# Onion_O2S_mPCIe.net
KiCad netlist of a schematic drawn in EAGLE
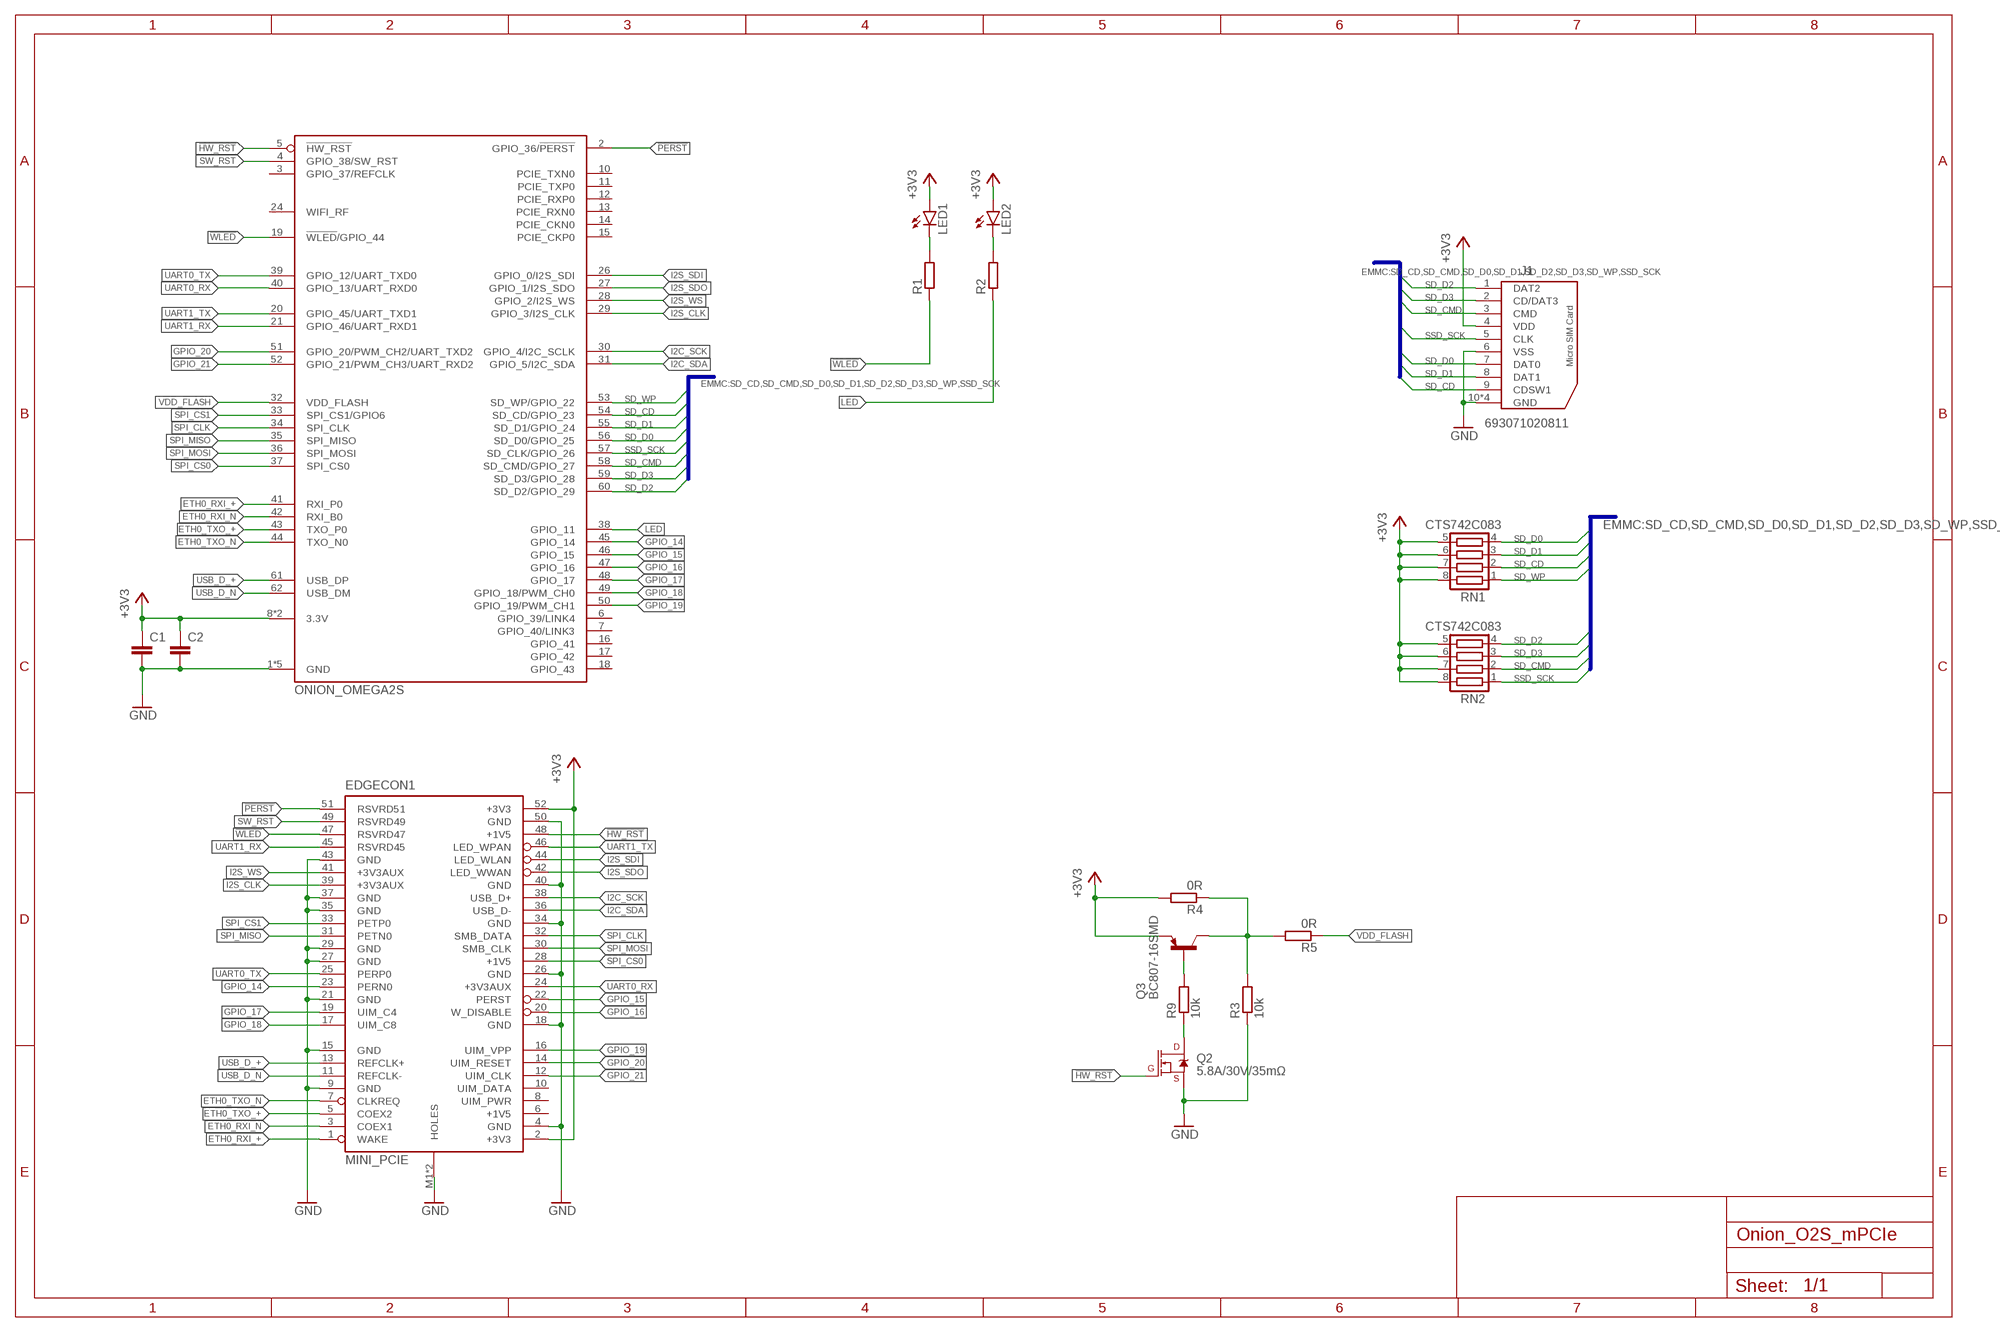
[diagram p0: schematic, sheet 1]

(export (version "E")
  (design (tool "Eeschema 10.0.6"))
  (components
    (comp (ref "C1")
      (value "C-EUC0603")
      (footprint "eagle-import:C0603")
      (libsource (lib "eagle-import") (part "C-EUC0603"))
    )
    (comp (ref "C2")
      (value "C-EUC0603")
      (footprint "eagle-import:C0603")
      (libsource (lib "eagle-import") (part "C-EUC0603"))
    )
    (comp (ref "EDGECON1")
      (value "MINI_PCIE")
      (footprint "eagle-import:MINI_PCIE")
      (libsource (lib "eagle-import") (part "MINI_PCIE"))
    )
    (comp (ref "J1")
      (value "693071020811")
      (footprint "eagle-import:693071020811")
      (libsource (lib "eagle-import") (part "693071020811"))
    )
    (comp (ref "LED1")
      (value "LEDCHIPLED_0603")
      (footprint "eagle-import:CHIPLED_0603")
      (libsource (lib "eagle-import") (part "LEDCHIPLED_0603"))
    )
    (comp (ref "LED2")
      (value "LEDCHIPLED_0603")
      (footprint "eagle-import:CHIPLED_0603")
      (libsource (lib "eagle-import") (part "LEDCHIPLED_0603"))
    )
    (comp (ref "Q2")
      (value "5.8A/30V/35mΩ")
      (footprint "eagle-import:SOT23-3")
      (libsource (lib "eagle-import") (part "MOSFET-NCH-AO3404A"))
    )
    (comp (ref "Q3")
      (value "BC807-16SMD")
      (footprint "eagle-import:SOT23-BEC")
      (libsource (lib "eagle-import") (part "BC807SMD-16"))
    )
    (comp (ref "R1")
      (value "R-EU_R0603")
      (footprint "eagle-import:R0603")
      (libsource (lib "eagle-import") (part "rcl_44894963_R-EU_R0603"))
    )
    (comp (ref "R2")
      (value "R-EU_R0603")
      (footprint "eagle-import:R0603")
      (libsource (lib "eagle-import") (part "rcl_44894963_R-EU_R0603"))
    )
    (comp (ref "R3")
      (value "10k")
      (footprint "eagle-import:R0603")
      (libsource (lib "eagle-import") (part "R-EU_R0603"))
    )
    (comp (ref "R4")
      (value "0R")
      (footprint "eagle-import:R0603")
      (libsource (lib "eagle-import") (part "R-EU_R0603"))
    )
    (comp (ref "R5")
      (value "0R")
      (footprint "eagle-import:R0603")
      (libsource (lib "eagle-import") (part "R-EU_R0603"))
    )
    (comp (ref "R9")
      (value "10k")
      (footprint "eagle-import:R0603")
      (libsource (lib "eagle-import") (part "R-EU_R0603"))
    )
    (comp (ref "RN1")
      (value "CTS742C083")
      (footprint "eagle-import:CTS742C083")
      (libsource (lib "eagle-import") (part "CTS742C083"))
    )
    (comp (ref "RN2")
      (value "CTS742C083")
      (footprint "eagle-import:CTS742C083")
      (libsource (lib "eagle-import") (part "CTS742C083"))
    )
    (comp (ref "U1")
      (value "ONION_OMEGA2S")
      (footprint "eagle-import:ONION_OMEGA2S")
      (libsource (lib "eagle-import") (part "ONION_OMEGA2S"))
    )
  )
  (nets
    (net (code "2") (name "+3V3") (class "Default")
      (node (ref "C1") (pin "1") (pinfunction "1_1") (pintype "passive"))
      (node (ref "C2") (pin "1") (pinfunction "1_1") (pintype "passive"))
      (node (ref "EDGECON1") (pin "2") (pinfunction "+3V3_2") (pintype "power_in"))
      (node (ref "EDGECON1") (pin "52") (pinfunction "+3V3_52") (pintype "power_in"))
      (node (ref "J1") (pin "4") (pinfunction "VDD_4") (pintype "bidirectional"))
      (node (ref "LED1") (pin "A") (pinfunction "A_A") (pintype "passive"))
      (node (ref "LED2") (pin "A") (pinfunction "A_A") (pintype "passive"))
      (node (ref "Q3") (pin "E") (pinfunction "E_E") (pintype "passive"))
      (node (ref "R4") (pin "2") (pinfunction "2_2") (pintype "passive"))
      (node (ref "RN1") (pin "5") (pinfunction "5_5") (pintype "passive"))
      (node (ref "RN1") (pin "6") (pinfunction "6_6") (pintype "passive"))
      (node (ref "RN1") (pin "7") (pinfunction "7_7") (pintype "passive"))
      (node (ref "RN1") (pin "8") (pinfunction "8_8") (pintype "passive"))
      (node (ref "RN2") (pin "5") (pinfunction "5_5") (pintype "passive"))
      (node (ref "RN2") (pin "6") (pinfunction "6_6") (pintype "passive"))
      (node (ref "RN2") (pin "7") (pinfunction "7_7") (pintype "passive"))
      (node (ref "RN2") (pin "8") (pinfunction "8_8") (pintype "passive"))
      (node (ref "U1") (pin "8") (pinfunction "3.3V_8") (pintype "bidirectional"))
      (node (ref "U1") (pin "9") (pinfunction "3.3V_9") (pintype "bidirectional"))
    )
    (net (code "3") (name "/+1V5") (class "Default")
      (node (ref "EDGECON1") (pin "6") (pinfunction "+1V5_6") (pintype "power_in"))
    )
    (net (code "4") (name "/SD_CD") (class "Default")
      (node (ref "J1") (pin "9") (pinfunction "CDSW1_9") (pintype "bidirectional"))
      (node (ref "RN1") (pin "2") (pinfunction "2_2") (pintype "passive"))
      (node (ref "U1") (pin "54") (pinfunction "SD_CD/GPIO_23_54") (pintype "bidirectional"))
    )
    (net (code "5") (name "/SD_CMD") (class "Default")
      (node (ref "J1") (pin "3") (pinfunction "CMD_3") (pintype "bidirectional"))
      (node (ref "RN2") (pin "2") (pinfunction "2_2") (pintype "passive"))
      (node (ref "U1") (pin "58") (pinfunction "SD_CMD/GPIO_27_58") (pintype "bidirectional"))
    )
    (net (code "6") (name "/SD_D0") (class "Default")
      (node (ref "J1") (pin "7") (pinfunction "DAT0_7") (pintype "bidirectional"))
      (node (ref "RN1") (pin "4") (pinfunction "4_4") (pintype "passive"))
      (node (ref "U1") (pin "56") (pinfunction "SD_D0/GPIO_25_56") (pintype "bidirectional"))
    )
    (net (code "7") (name "/SD_D1") (class "Default")
      (node (ref "J1") (pin "8") (pinfunction "DAT1_8") (pintype "bidirectional"))
      (node (ref "RN1") (pin "3") (pinfunction "3_3") (pintype "passive"))
      (node (ref "U1") (pin "55") (pinfunction "SD_D1/GPIO_24_55") (pintype "bidirectional"))
    )
    (net (code "8") (name "/SD_D2") (class "Default")
      (node (ref "J1") (pin "1") (pinfunction "DAT2_1") (pintype "bidirectional"))
      (node (ref "RN2") (pin "4") (pinfunction "4_4") (pintype "passive"))
      (node (ref "U1") (pin "60") (pinfunction "SD_D2/GPIO_29_60") (pintype "bidirectional"))
    )
    (net (code "9") (name "/SD_D3") (class "Default")
      (node (ref "J1") (pin "2") (pinfunction "CD/DAT3_2") (pintype "bidirectional"))
      (node (ref "RN2") (pin "3") (pinfunction "3_3") (pintype "passive"))
      (node (ref "U1") (pin "59") (pinfunction "SD_D3/GPIO_28_59") (pintype "bidirectional"))
    )
    (net (code "10") (name "/SD_WP") (class "Default")
      (node (ref "RN1") (pin "1") (pinfunction "1_1") (pintype "passive"))
      (node (ref "U1") (pin "53") (pinfunction "SD_WP/GPIO_22_53") (pintype "bidirectional"))
    )
    (net (code "11") (name "/SSD_SCK") (class "Default")
      (node (ref "J1") (pin "5") (pinfunction "CLK_5") (pintype "bidirectional"))
      (node (ref "RN2") (pin "1") (pinfunction "1_1") (pintype "passive"))
      (node (ref "U1") (pin "57") (pinfunction "SD_CLK/GPIO_26_57") (pintype "bidirectional"))
    )
    (net (code "13") (name "/~{HW_RST}") (class "Default")
      (node (ref "EDGECON1") (pin "48") (pinfunction "+1V5_48") (pintype "output"))
      (node (ref "Q2") (pin "1") (pinfunction "G_1") (pintype "bidirectional"))
      (node (ref "U1") (pin "5") (pinfunction "~{HW_RST}_5") (pintype "bidirectional"))
    )
    (net (code "14") (name "/~{PERST}") (class "Default")
      (node (ref "EDGECON1") (pin "51") (pinfunction "RSVRD51_51") (pintype "bidirectional"))
      (node (ref "U1") (pin "2") (pinfunction "GPIO_36/~{PERST}_2") (pintype "bidirectional"))
    )
    (net (code "15") (name "/~{WLED}") (class "Default")
      (node (ref "EDGECON1") (pin "47") (pinfunction "RSVRD47_47") (pintype "bidirectional"))
      (node (ref "R1") (pin "1") (pinfunction "1_1") (pintype "passive"))
      (node (ref "U1") (pin "19") (pinfunction "~{WLED}/GPIO_44_19") (pintype "bidirectional"))
    )
    (net (code "16") (name "ETH0_RXI_+") (class "Default")
      (node (ref "EDGECON1") (pin "1") (pinfunction "WAKE_1") (pintype "output"))
      (node (ref "U1") (pin "41") (pinfunction "RXI_P0_41") (pintype "bidirectional"))
    )
    (net (code "17") (name "ETH0_RXI_N") (class "Default")
      (node (ref "EDGECON1") (pin "3") (pinfunction "COEX1_3") (pintype "bidirectional"))
      (node (ref "U1") (pin "42") (pinfunction "RXI_B0_42") (pintype "bidirectional"))
    )
    (net (code "18") (name "ETH0_TXO_+") (class "Default")
      (node (ref "EDGECON1") (pin "5") (pinfunction "COEX2_5") (pintype "bidirectional"))
      (node (ref "U1") (pin "43") (pinfunction "TXO_P0_43") (pintype "bidirectional"))
    )
    (net (code "19") (name "ETH0_TXO_N") (class "Default")
      (node (ref "EDGECON1") (pin "7") (pinfunction "CLKREQ_7") (pintype "output"))
      (node (ref "U1") (pin "44") (pinfunction "TXO_N0_44") (pintype "bidirectional"))
    )
    (net (code "20") (name "GND") (class "Default")
      (node (ref "C1") (pin "2") (pinfunction "2_2") (pintype "passive"))
      (node (ref "C2") (pin "2") (pinfunction "2_2") (pintype "passive"))
      (node (ref "EDGECON1") (pin "15") (pinfunction "GND_15") (pintype "power_in"))
      (node (ref "EDGECON1") (pin "18") (pinfunction "GND_18") (pintype "power_in"))
      (node (ref "EDGECON1") (pin "21") (pinfunction "GND_21") (pintype "power_in"))
      (node (ref "EDGECON1") (pin "26") (pinfunction "GND_26") (pintype "power_in"))
      (node (ref "EDGECON1") (pin "27") (pinfunction "GND_27") (pintype "power_in"))
      (node (ref "EDGECON1") (pin "29") (pinfunction "GND_29") (pintype "power_in"))
      (node (ref "EDGECON1") (pin "34") (pinfunction "GND_34") (pintype "bidirectional"))
      (node (ref "EDGECON1") (pin "35") (pinfunction "GND_35") (pintype "power_in"))
      (node (ref "EDGECON1") (pin "37") (pinfunction "GND_37") (pintype "bidirectional"))
      (node (ref "EDGECON1") (pin "4") (pinfunction "GND_4") (pintype "power_in"))
      (node (ref "EDGECON1") (pin "40") (pinfunction "GND_40") (pintype "bidirectional"))
      (node (ref "EDGECON1") (pin "43") (pinfunction "GND_43") (pintype "bidirectional"))
      (node (ref "EDGECON1") (pin "50") (pinfunction "GND_50") (pintype "output"))
      (node (ref "EDGECON1") (pin "9") (pinfunction "GND_9") (pintype "power_in"))
      (node (ref "EDGECON1") (pin "M1") (pinfunction "HOLES_M1") (pintype "bidirectional"))
      (node (ref "EDGECON1") (pin "M2") (pinfunction "HOLES_M2") (pintype "bidirectional"))
      (node (ref "J1") (pin "10") (pinfunction "GND_10") (pintype "bidirectional"))
      (node (ref "J1") (pin "11") (pinfunction "GND_11") (pintype "bidirectional"))
      (node (ref "J1") (pin "12") (pinfunction "GND_12") (pintype "bidirectional"))
      (node (ref "J1") (pin "13") (pinfunction "GND_13") (pintype "bidirectional"))
      (node (ref "J1") (pin "6") (pinfunction "VSS_6") (pintype "bidirectional"))
      (node (ref "Q2") (pin "2") (pinfunction "S_2") (pintype "bidirectional"))
      (node (ref "R3") (pin "1") (pinfunction "1_1") (pintype "passive"))
      (node (ref "U1") (pin "1") (pinfunction "GND_1") (pintype "bidirectional"))
      (node (ref "U1") (pin "22") (pinfunction "GND_22") (pintype "bidirectional"))
      (node (ref "U1") (pin "23") (pinfunction "GND_23") (pintype "bidirectional"))
      (node (ref "U1") (pin "25") (pinfunction "GND_25") (pintype "bidirectional"))
      (node (ref "U1") (pin "63") (pinfunction "GND_63") (pintype "bidirectional"))
    )
    (net (code "21") (name "GPIO_14") (class "Default")
      (node (ref "EDGECON1") (pin "23") (pinfunction "PERN0_23") (pintype "bidirectional"))
      (node (ref "U1") (pin "45") (pinfunction "GPIO_14_45") (pintype "bidirectional"))
    )
    (net (code "22") (name "GPIO_15") (class "Default")
      (node (ref "EDGECON1") (pin "22") (pinfunction "PERST_22") (pintype "input"))
      (node (ref "U1") (pin "46") (pinfunction "GPIO_15_46") (pintype "bidirectional"))
    )
    (net (code "23") (name "GPIO_16") (class "Default")
      (node (ref "EDGECON1") (pin "20") (pinfunction "W_DISABLE_20") (pintype "input"))
      (node (ref "U1") (pin "47") (pinfunction "GPIO_16_47") (pintype "bidirectional"))
    )
    (net (code "24") (name "GPIO_17") (class "Default")
      (node (ref "EDGECON1") (pin "19") (pinfunction "UIM_C4_19") (pintype "bidirectional"))
      (node (ref "U1") (pin "48") (pinfunction "GPIO_17_48") (pintype "bidirectional"))
    )
    (net (code "25") (name "GPIO_18") (class "Default")
      (node (ref "EDGECON1") (pin "17") (pinfunction "UIM_C8_17") (pintype "bidirectional"))
      (node (ref "U1") (pin "49") (pinfunction "GPIO_18/PWM_CH0_49") (pintype "bidirectional"))
    )
    (net (code "26") (name "GPIO_19") (class "Default")
      (node (ref "EDGECON1") (pin "16") (pinfunction "UIM_VPP_16") (pintype "bidirectional"))
      (node (ref "U1") (pin "50") (pinfunction "GPIO_19/PWM_CH1_50") (pintype "bidirectional"))
    )
    (net (code "27") (name "GPIO_20") (class "Default")
      (node (ref "EDGECON1") (pin "14") (pinfunction "UIM_RESET_14") (pintype "bidirectional"))
      (node (ref "U1") (pin "51") (pinfunction "GPIO_20/PWM_CH2/UART_TXD2_51") (pintype "bidirectional"))
    )
    (net (code "28") (name "GPIO_21") (class "Default")
      (node (ref "EDGECON1") (pin "12") (pinfunction "UIM_CLK_12") (pintype "bidirectional"))
      (node (ref "U1") (pin "52") (pinfunction "GPIO_21/PWM_CH3/UART_RXD2_52") (pintype "bidirectional"))
    )
    (net (code "29") (name "I2C_SCK") (class "Default")
      (node (ref "EDGECON1") (pin "38") (pinfunction "USB_D+_38") (pintype "power_in"))
      (node (ref "U1") (pin "30") (pinfunction "GPIO_4/I2C_SCLK_30") (pintype "bidirectional"))
    )
    (net (code "30") (name "I2C_SDA") (class "Default")
      (node (ref "EDGECON1") (pin "36") (pinfunction "USB_D-_36") (pintype "bidirectional"))
      (node (ref "U1") (pin "31") (pinfunction "GPIO_5/I2C_SDA_31") (pintype "bidirectional"))
    )
    (net (code "31") (name "I2S_CLK") (class "Default")
      (node (ref "EDGECON1") (pin "39") (pinfunction "+3V3AUX_39") (pintype "bidirectional"))
      (node (ref "U1") (pin "29") (pinfunction "GPIO_3/I2S_CLK_29") (pintype "bidirectional"))
    )
    (net (code "32") (name "I2S_SDI") (class "Default")
      (node (ref "EDGECON1") (pin "44") (pinfunction "LED_WLAN_44") (pintype "output"))
      (node (ref "U1") (pin "26") (pinfunction "GPIO_0/I2S_SDI_26") (pintype "bidirectional"))
    )
    (net (code "33") (name "I2S_SDO") (class "Default")
      (node (ref "EDGECON1") (pin "42") (pinfunction "LED_WWAN_42") (pintype "output"))
      (node (ref "U1") (pin "27") (pinfunction "GPIO_1/I2S_SDO_27") (pintype "bidirectional"))
    )
    (net (code "34") (name "I2S_WS") (class "Default")
      (node (ref "EDGECON1") (pin "41") (pinfunction "+3V3AUX_41") (pintype "bidirectional"))
      (node (ref "U1") (pin "28") (pinfunction "GPIO_2/I2S_WS_28") (pintype "bidirectional"))
    )
    (net (code "35") (name "LED") (class "Default")
      (node (ref "R2") (pin "1") (pinfunction "1_1") (pintype "passive"))
      (node (ref "U1") (pin "38") (pinfunction "GPIO_11_38") (pintype "bidirectional"))
    )
    (net (code "36") (name "Net-(LED1-PadC)") (class "Default")
      (node (ref "LED1") (pin "C") (pinfunction "C_C") (pintype "passive"))
      (node (ref "R1") (pin "2") (pinfunction "2_2") (pintype "passive"))
    )
    (net (code "37") (name "Net-(LED2-PadC)") (class "Default")
      (node (ref "LED2") (pin "C") (pinfunction "C_C") (pintype "passive"))
      (node (ref "R2") (pin "2") (pinfunction "2_2") (pintype "passive"))
    )
    (net (code "38") (name "Net-(Q2-D)") (class "Default")
      (node (ref "Q2") (pin "3") (pinfunction "D_3") (pintype "bidirectional"))
      (node (ref "R9") (pin "1") (pinfunction "1_1") (pintype "passive"))
    )
    (net (code "39") (name "Net-(Q3-PadB)") (class "Default")
      (node (ref "Q3") (pin "B") (pinfunction "B_B") (pintype "passive"))
      (node (ref "R9") (pin "2") (pinfunction "2_2") (pintype "passive"))
    )
    (net (code "40") (name "Net-(Q3-PadC)") (class "Default")
      (node (ref "Q3") (pin "C") (pinfunction "C_C") (pintype "passive"))
      (node (ref "R3") (pin "2") (pinfunction "2_2") (pintype "passive"))
      (node (ref "R4") (pin "1") (pinfunction "1_1") (pintype "passive"))
      (node (ref "R5") (pin "2") (pinfunction "2_2") (pintype "passive"))
    )
    (net (code "41") (name "SPI_CLK") (class "Default")
      (node (ref "EDGECON1") (pin "32") (pinfunction "SMB_DATA_32") (pintype "power_in"))
      (node (ref "U1") (pin "34") (pinfunction "SPI_CLK_34") (pintype "bidirectional"))
    )
    (net (code "42") (name "SPI_CS0") (class "Default")
      (node (ref "EDGECON1") (pin "28") (pinfunction "+1V5_28") (pintype "power_in"))
      (node (ref "U1") (pin "37") (pinfunction "SPI_CS0_37") (pintype "bidirectional"))
    )
    (net (code "43") (name "SPI_CS1") (class "Default")
      (node (ref "EDGECON1") (pin "33") (pinfunction "PETP0_33") (pintype "bidirectional"))
      (node (ref "U1") (pin "33") (pinfunction "SPI_CS1/GPIO6_33") (pintype "bidirectional"))
    )
    (net (code "44") (name "SPI_MISO") (class "Default")
      (node (ref "EDGECON1") (pin "31") (pinfunction "PETN0_31") (pintype "bidirectional"))
      (node (ref "U1") (pin "35") (pinfunction "SPI_MISO_35") (pintype "bidirectional"))
    )
    (net (code "45") (name "SPI_MOSI") (class "Default")
      (node (ref "EDGECON1") (pin "30") (pinfunction "SMB_CLK_30") (pintype "input"))
      (node (ref "U1") (pin "36") (pinfunction "SPI_MOSI_36") (pintype "bidirectional"))
    )
    (net (code "46") (name "SW_RST") (class "Default")
      (node (ref "EDGECON1") (pin "49") (pinfunction "RSVRD49_49") (pintype "bidirectional"))
      (node (ref "U1") (pin "4") (pinfunction "GPIO_38/SW_RST_4") (pintype "bidirectional"))
    )
    (net (code "47") (name "UART0_RX") (class "Default")
      (node (ref "EDGECON1") (pin "24") (pinfunction "+3V3AUX_24") (pintype "power_in"))
      (node (ref "U1") (pin "40") (pinfunction "GPIO_13/UART_RXD0_40") (pintype "bidirectional"))
    )
    (net (code "48") (name "UART0_TX") (class "Default")
      (node (ref "EDGECON1") (pin "25") (pinfunction "PERP0_25") (pintype "bidirectional"))
      (node (ref "U1") (pin "39") (pinfunction "GPIO_12/UART_TXD0_39") (pintype "bidirectional"))
    )
    (net (code "49") (name "UART1_RX") (class "Default")
      (node (ref "EDGECON1") (pin "45") (pinfunction "RSVRD45_45") (pintype "bidirectional"))
      (node (ref "U1") (pin "21") (pinfunction "GPIO_46/UART_RXD1_21") (pintype "bidirectional"))
    )
    (net (code "50") (name "UART1_TX") (class "Default")
      (node (ref "EDGECON1") (pin "46") (pinfunction "LED_WPAN_46") (pintype "output"))
      (node (ref "U1") (pin "20") (pinfunction "GPIO_45/UART_TXD1_20") (pintype "bidirectional"))
    )
    (net (code "51") (name "USB_D_+") (class "Default")
      (node (ref "EDGECON1") (pin "13") (pinfunction "REFCLK+_13") (pintype "input"))
      (node (ref "U1") (pin "61") (pinfunction "USB_DP_61") (pintype "bidirectional"))
    )
    (net (code "52") (name "USB_D_N") (class "Default")
      (node (ref "EDGECON1") (pin "11") (pinfunction "REFCLK-_11") (pintype "input"))
      (node (ref "U1") (pin "62") (pinfunction "USB_DM_62") (pintype "bidirectional"))
    )
    (net (code "53") (name "VDD_FLASH") (class "Default")
      (node (ref "R5") (pin "1") (pinfunction "1_1") (pintype "passive"))
      (node (ref "U1") (pin "32") (pinfunction "VDD_FLASH_32") (pintype "bidirectional"))
    )
    (net (code "54") (name "unconnected-(EDGECON1-UIM_DATA-Pad10)") (class "Default")
      (node (ref "EDGECON1") (pin "10") (pinfunction "UIM_DATA_10") (pintype "bidirectional"))
    )
    (net (code "55") (name "unconnected-(EDGECON1-UIM_PWR-Pad8)") (class "Default")
      (node (ref "EDGECON1") (pin "8") (pinfunction "UIM_PWR_8") (pintype "bidirectional"))
    )
    (net (code "56") (name "unconnected-(U1-GPIO_37{slash}REFCLK-Pad3)") (class "Default")
      (node (ref "U1") (pin "3") (pinfunction "GPIO_37/REFCLK_3") (pintype "bidirectional"))
    )
    (net (code "57") (name "unconnected-(U1-GPIO_39{slash}LINK4-Pad6)") (class "Default")
      (node (ref "U1") (pin "6") (pinfunction "GPIO_39/LINK4_6") (pintype "bidirectional"))
    )
    (net (code "58") (name "unconnected-(U1-GPIO_40{slash}LINK3-Pad7)") (class "Default")
      (node (ref "U1") (pin "7") (pinfunction "GPIO_40/LINK3_7") (pintype "bidirectional"))
    )
    (net (code "59") (name "unconnected-(U1-GPIO_41-Pad16)") (class "Default")
      (node (ref "U1") (pin "16") (pinfunction "GPIO_41_16") (pintype "bidirectional"))
    )
    (net (code "60") (name "unconnected-(U1-GPIO_42-Pad17)") (class "Default")
      (node (ref "U1") (pin "17") (pinfunction "GPIO_42_17") (pintype "bidirectional"))
    )
    (net (code "61") (name "unconnected-(U1-GPIO_43-Pad18)") (class "Default")
      (node (ref "U1") (pin "18") (pinfunction "GPIO_43_18") (pintype "bidirectional"))
    )
    (net (code "62") (name "unconnected-(U1-PCIE_CKN0-Pad14)") (class "Default")
      (node (ref "U1") (pin "14") (pinfunction "PCIE_CKN0_14") (pintype "bidirectional"))
    )
    (net (code "63") (name "unconnected-(U1-PCIE_CKP0-Pad15)") (class "Default")
      (node (ref "U1") (pin "15") (pinfunction "PCIE_CKP0_15") (pintype "bidirectional"))
    )
    (net (code "64") (name "unconnected-(U1-PCIE_RXN0-Pad13)") (class "Default")
      (node (ref "U1") (pin "13") (pinfunction "PCIE_RXN0_13") (pintype "bidirectional"))
    )
    (net (code "65") (name "unconnected-(U1-PCIE_RXP0-Pad12)") (class "Default")
      (node (ref "U1") (pin "12") (pinfunction "PCIE_RXP0_12") (pintype "bidirectional"))
    )
    (net (code "66") (name "unconnected-(U1-PCIE_TXN0-Pad10)") (class "Default")
      (node (ref "U1") (pin "10") (pinfunction "PCIE_TXN0_10") (pintype "bidirectional"))
    )
    (net (code "67") (name "unconnected-(U1-PCIE_TXP0-Pad11)") (class "Default")
      (node (ref "U1") (pin "11") (pinfunction "PCIE_TXP0_11") (pintype "bidirectional"))
    )
    (net (code "68") (name "unconnected-(U1-WIFI_RF-Pad24)") (class "Default")
      (node (ref "U1") (pin "24") (pinfunction "WIFI_RF_24") (pintype "bidirectional"))
    )
  )
)
